# Debug.net
KiCad netlist of a schematic drawn in Altium Designer
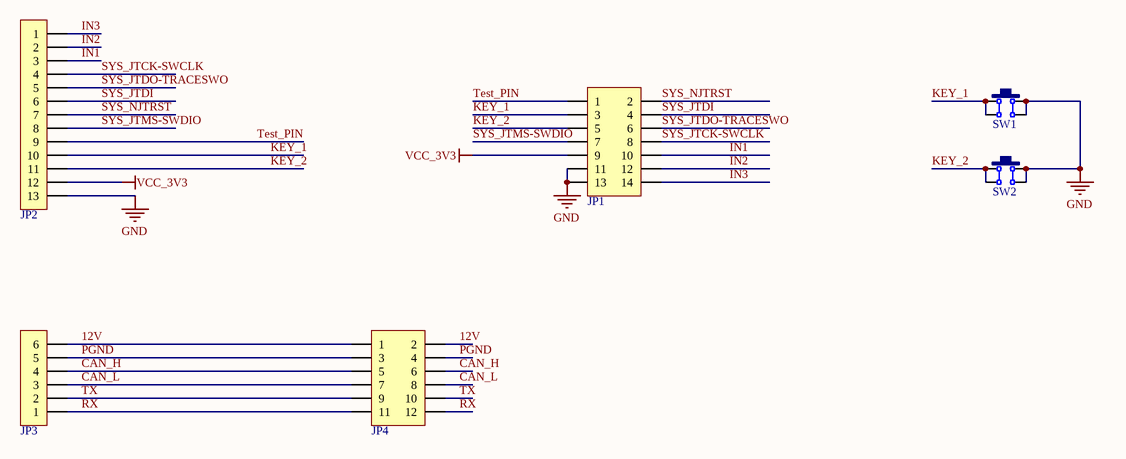
[diagram p0: Debug.SchDoc]

(export (version "E")
  (design (tool "Eeschema 10.0.6"))
  (components
    (comp (ref "JP1")
      (value "Header 2X7")
      (footprint "HDR2.54-LI-2x7P")
      (description "7*2P接插件")
      (libsource (lib "5.3 - 接插件-脚距2.54 (100mil) ") (part "Header 7X2"))
    )
    (comp (ref "JP2")
      (value "HDR-1X13")
      (footprint "FPC0.5-WT-13P")
      (description "13P连接器")
      (libsource (lib "5.1 - 1.25mm连接器(FPC1.25_GH1.25_MX1.25)") (part "Header 13"))
    )
    (comp (ref "JP3")
      (value "HDR-1X6")
      (footprint "GH-1.25-6P")
      (description "6P接插件")
      (libsource (lib "5.0 - 接插件-脚距1.25") (part "Header 6"))
    )
    (comp (ref "JP4")
      (value "Header 6X2")
      (footprint "HDR2.54-LI-2x6P")
      (description "6*2P接插件")
      (libsource (lib "5.3 - 接插件-脚距2.54 (100mil) ") (part "Header  6X2"))
    )
    (comp (ref "SW1")
      (value "6x6x5")
      (footprint "TSW SMD-3*6*4.3")
      (description "贴片6x6轻触开关")
      (libsource (lib "0.7 - 常用按键-开关") (part "TSW SMD-6x6"))
    )
    (comp (ref "SW2")
      (value "6x6x5")
      (footprint "TSW SMD-3*6*4.3")
      (description "贴片6x6轻触开关")
      (libsource (lib "0.7 - 常用按键-开关") (part "TSW SMD-6x6"))
    )
  )
  (nets
    (net (code "1") (name "/12V") (class "Default")
      (node (ref "JP3") (pin "6") (pinfunction "6_6") (pintype "passive"))
      (node (ref "JP4") (pin "1") (pinfunction "1_1") (pintype "passive"))
      (node (ref "JP4") (pin "2") (pinfunction "2_2") (pintype "passive"))
    )
    (net (code "2") (name "/CAN_H") (class "Default")
      (node (ref "JP3") (pin "4") (pinfunction "4_4") (pintype "passive"))
      (node (ref "JP4") (pin "5") (pinfunction "5_5") (pintype "passive"))
      (node (ref "JP4") (pin "6") (pinfunction "6_6") (pintype "passive"))
    )
    (net (code "3") (name "/CAN_L") (class "Default")
      (node (ref "JP3") (pin "3") (pinfunction "3_3") (pintype "passive"))
      (node (ref "JP4") (pin "7") (pinfunction "7_7") (pintype "passive"))
      (node (ref "JP4") (pin "8") (pinfunction "8_8") (pintype "passive"))
    )
    (net (code "4") (name "/IN1") (class "Default")
      (node (ref "JP1") (pin "10") (pinfunction "10_10") (pintype "passive"))
      (node (ref "JP2") (pin "3") (pinfunction "3_3") (pintype "passive"))
    )
    (net (code "5") (name "/IN2") (class "Default")
      (node (ref "JP1") (pin "12") (pinfunction "12_12") (pintype "passive"))
      (node (ref "JP2") (pin "2") (pinfunction "2_2") (pintype "passive"))
    )
    (net (code "6") (name "/IN3") (class "Default")
      (node (ref "JP1") (pin "14") (pinfunction "14_14") (pintype "passive"))
      (node (ref "JP2") (pin "1") (pinfunction "1_1") (pintype "passive"))
    )
    (net (code "7") (name "/KEY_1") (class "Default")
      (node (ref "JP1") (pin "3") (pinfunction "3_3") (pintype "passive"))
      (node (ref "JP2") (pin "10") (pinfunction "10_10") (pintype "passive"))
      (node (ref "SW1") (pin "1") (pinfunction "1_1") (pintype "passive"))
    )
    (net (code "8") (name "/KEY_2") (class "Default")
      (node (ref "JP1") (pin "5") (pinfunction "5_5") (pintype "passive"))
      (node (ref "JP2") (pin "11") (pinfunction "11_11") (pintype "passive"))
      (node (ref "SW2") (pin "1") (pinfunction "1_1") (pintype "passive"))
    )
    (net (code "9") (name "/PGND") (class "Default")
      (node (ref "JP3") (pin "5") (pinfunction "5_5") (pintype "passive"))
      (node (ref "JP4") (pin "3") (pinfunction "3_3") (pintype "passive"))
      (node (ref "JP4") (pin "4") (pinfunction "4_4") (pintype "passive"))
    )
    (net (code "10") (name "/RX") (class "Default")
      (node (ref "JP3") (pin "1") (pinfunction "1_1") (pintype "passive"))
      (node (ref "JP4") (pin "11") (pinfunction "11_11") (pintype "passive"))
      (node (ref "JP4") (pin "12") (pinfunction "12_12") (pintype "passive"))
    )
    (net (code "11") (name "/SYS_JTCK-SWCLK") (class "Default")
      (node (ref "JP1") (pin "8") (pinfunction "8_8") (pintype "passive"))
      (node (ref "JP2") (pin "4") (pinfunction "4_4") (pintype "passive"))
    )
    (net (code "12") (name "/SYS_JTDI") (class "Default")
      (node (ref "JP1") (pin "4") (pinfunction "4_4") (pintype "passive"))
      (node (ref "JP2") (pin "6") (pinfunction "6_6") (pintype "passive"))
    )
    (net (code "13") (name "/SYS_JTDO-TRACESWO") (class "Default")
      (node (ref "JP1") (pin "6") (pinfunction "6_6") (pintype "passive"))
      (node (ref "JP2") (pin "5") (pinfunction "5_5") (pintype "passive"))
    )
    (net (code "14") (name "/SYS_JTMS-SWDIO") (class "Default")
      (node (ref "JP1") (pin "7") (pinfunction "7_7") (pintype "passive"))
      (node (ref "JP2") (pin "8") (pinfunction "8_8") (pintype "passive"))
    )
    (net (code "15") (name "/SYS_NJTRST") (class "Default")
      (node (ref "JP1") (pin "2") (pinfunction "2_2") (pintype "passive"))
      (node (ref "JP2") (pin "7") (pinfunction "7_7") (pintype "passive"))
    )
    (net (code "16") (name "/TX") (class "Default")
      (node (ref "JP3") (pin "2") (pinfunction "2_2") (pintype "passive"))
      (node (ref "JP4") (pin "10") (pinfunction "10_10") (pintype "passive"))
      (node (ref "JP4") (pin "9") (pinfunction "9_9") (pintype "passive"))
    )
    (net (code "17") (name "/Test_PIN") (class "Default")
      (node (ref "JP1") (pin "1") (pinfunction "1_1") (pintype "passive"))
      (node (ref "JP2") (pin "9") (pinfunction "9_9") (pintype "passive"))
    )
    (net (code "18") (name "GND") (class "Default")
      (node (ref "JP1") (pin "11") (pinfunction "11_11") (pintype "passive"))
      (node (ref "JP1") (pin "13") (pinfunction "13_13") (pintype "passive"))
      (node (ref "JP2") (pin "13") (pinfunction "13_13") (pintype "passive"))
      (node (ref "SW1") (pin "2") (pinfunction "2_2") (pintype "passive"))
      (node (ref "SW2") (pin "2") (pinfunction "2_2") (pintype "passive"))
    )
    (net (code "19") (name "VCC_3V3") (class "Default")
      (node (ref "JP1") (pin "9") (pinfunction "9_9") (pintype "passive"))
      (node (ref "JP2") (pin "12") (pinfunction "12_12") (pintype "passive"))
    )
  )
)
